# backscatter_tag_v2.net
KiCad netlist of a schematic drawn in EAGLE
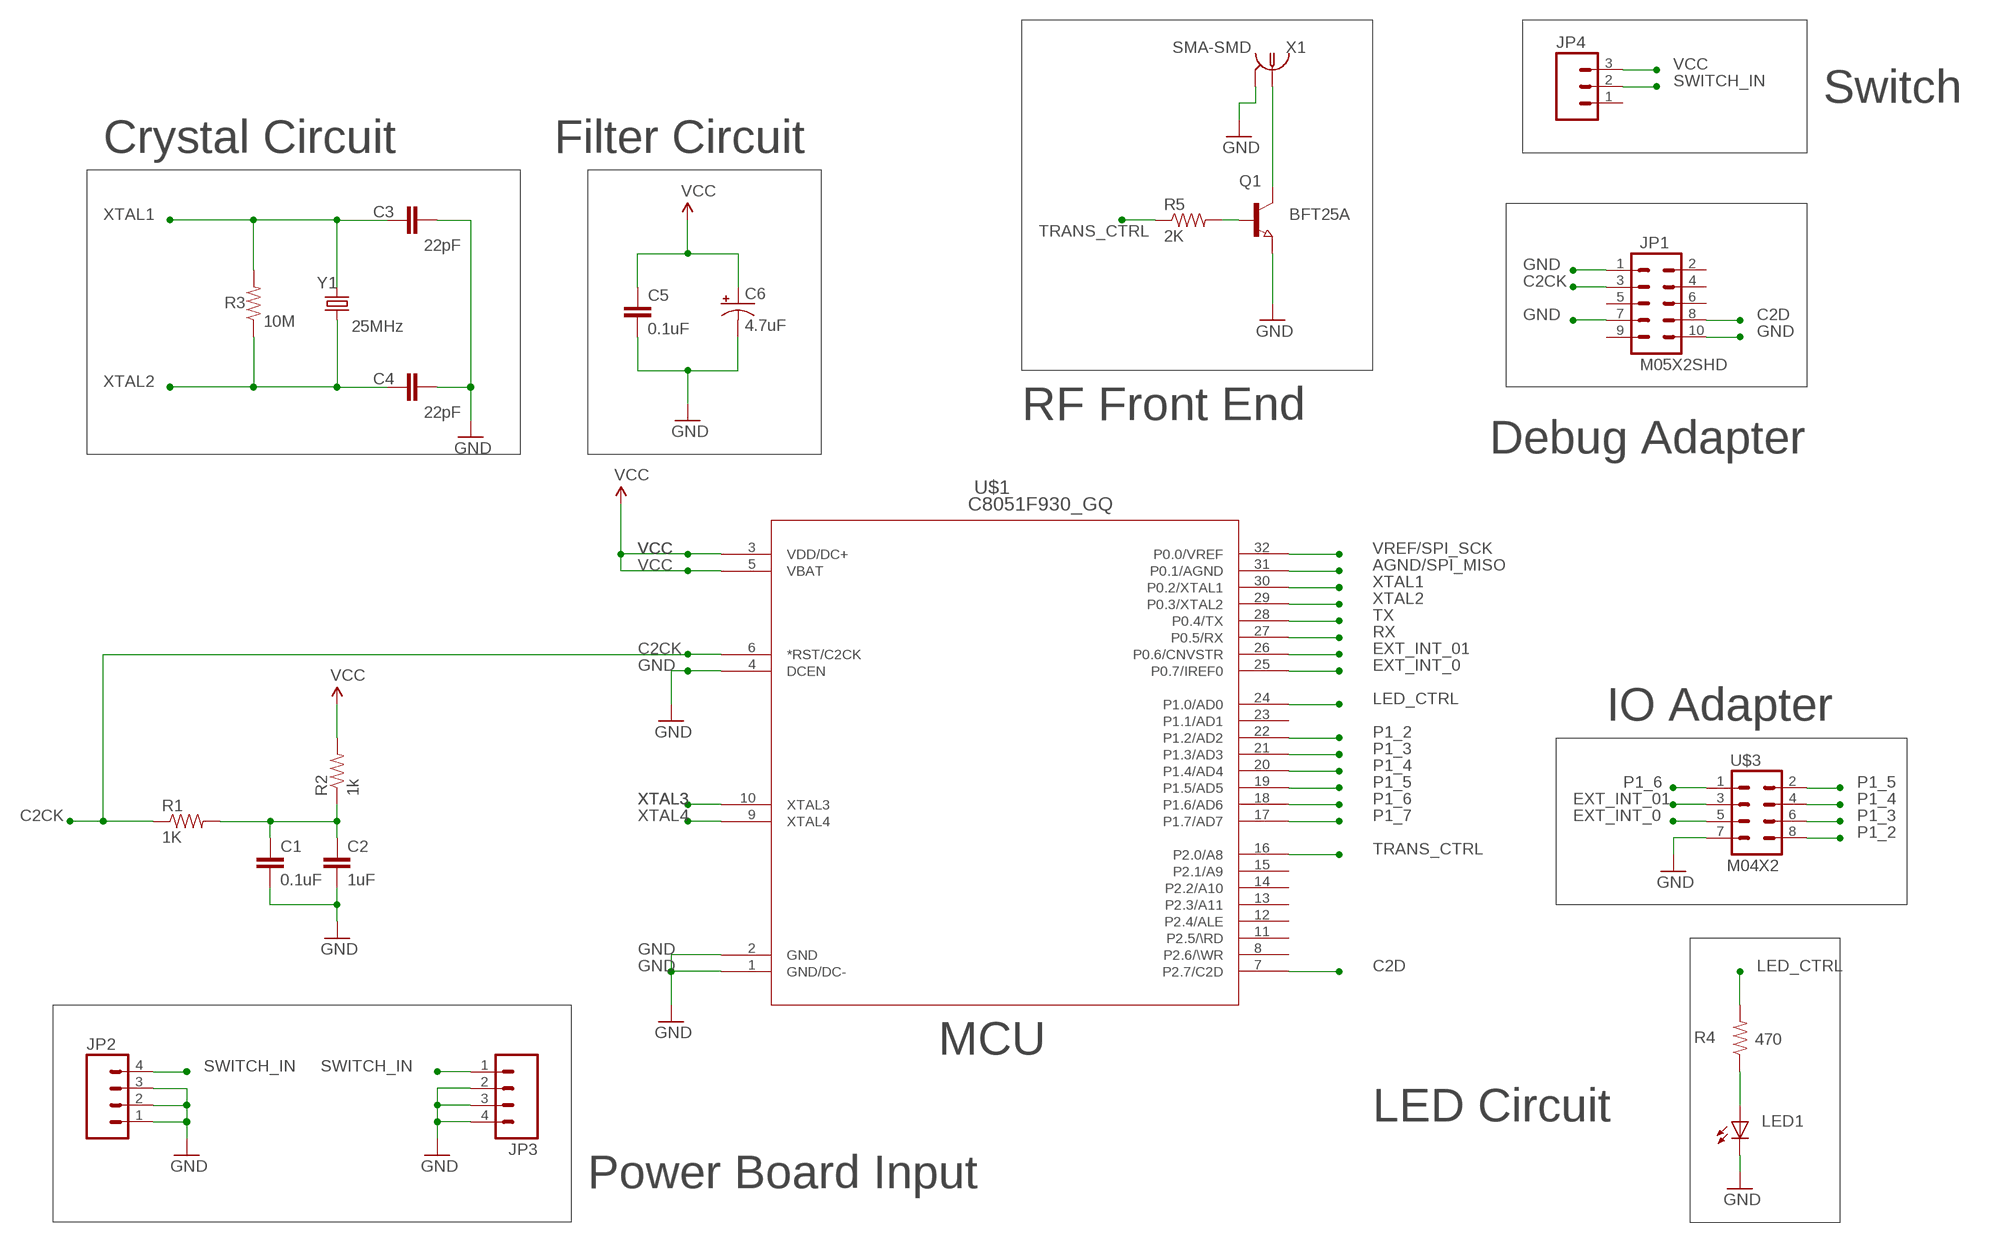
[diagram p0: schematic, sheet 1]

(export (version "E")
  (design (tool "Eeschema 10.0.6"))
  (components
    (comp (ref "C1")
      (value "0.1uF")
      (footprint "eagle-import:0805")
      (libsource (lib "eagle-import") (part "CAP0805"))
    )
    (comp (ref "C2")
      (value "1uF")
      (footprint "eagle-import:0805")
      (libsource (lib "eagle-import") (part "CAP0805"))
    )
    (comp (ref "C3")
      (value "22pF")
      (footprint "eagle-import:0805")
      (libsource (lib "eagle-import") (part "SparkFun-Capacitors_CAP0805"))
    )
    (comp (ref "C4")
      (value "22pF")
      (footprint "eagle-import:0805")
      (libsource (lib "eagle-import") (part "SparkFun-Capacitors_CAP0805"))
    )
    (comp (ref "C5")
      (value "0.1uF")
      (footprint "eagle-import:0805")
      (libsource (lib "eagle-import") (part "SparkFun-Capacitors_CAP0805"))
    )
    (comp (ref "C6")
      (value "4.7uF")
      (footprint "eagle-import:EIA3216")
      (libsource (lib "eagle-import") (part "CAP_POL1206"))
    )
    (comp (ref "JP1")
      (value "M05X2SHD")
      (footprint "eagle-import:2X5-SHROUDED")
      (libsource (lib "eagle-import") (part "M05X2SHD"))
    )
    (comp (ref "JP2")
      (value "M04LOCK")
      (footprint "eagle-import:1X04_LOCK")
      (libsource (lib "eagle-import") (part "M04LOCK"))
    )
    (comp (ref "JP3")
      (value "M04LOCK")
      (footprint "eagle-import:1X04_LOCK")
      (libsource (lib "eagle-import") (part "M04LOCK"))
    )
    (comp (ref "JP4")
      (value "M03LOCK")
      (footprint "eagle-import:1X03_LOCK")
      (libsource (lib "eagle-import") (part "M03LOCK"))
    )
    (comp (ref "LED1")
      (value "LED-FKIT-1206")
      (footprint "eagle-import:FKIT-LED-1206")
      (libsource (lib "eagle-import") (part "LED-FKIT-1206"))
    )
    (comp (ref "Q1")
      (value "BFT25A")
      (footprint "eagle-import:SOT23")
      (libsource (lib "eagle-import") (part "NPN-TRANSISTOR_SOT23"))
    )
    (comp (ref "R1")
      (value "1K")
      (footprint "eagle-import:0805")
      (libsource (lib "eagle-import") (part "RESISTOR0805-RES"))
    )
    (comp (ref "R2")
      (value "1k")
      (footprint "eagle-import:0805")
      (libsource (lib "eagle-import") (part "RESISTOR0805-RES"))
    )
    (comp (ref "R3")
      (value "10M")
      (footprint "eagle-import:0805")
      (libsource (lib "eagle-import") (part "SparkFun-Resistors_RESISTOR0805-RES"))
    )
    (comp (ref "R4")
      (value "470")
      (footprint "eagle-import:0805")
      (libsource (lib "eagle-import") (part "SparkFun-Resistors_RESISTOR0805-RES"))
    )
    (comp (ref "R5")
      (value "2K")
      (footprint "eagle-import:0603-RES")
      (libsource (lib "eagle-import") (part "SparkFun-Resistors_RESISTOR0603-RES"))
    )
    (comp (ref "U$1")
      (value "C8051F930_GQ")
      (footprint "eagle-import:QFP32-7X7-0P8MM")
      (libsource (lib "eagle-import") (part "C8051F930_GQ"))
    )
    (comp (ref "U$3")
      (value "M04X2")
      (footprint "eagle-import:2X4")
      (libsource (lib "eagle-import") (part "M04X2"))
    )
    (comp (ref "X1")
      (value "SMA-SMD")
      (footprint "eagle-import:SMA-SMD")
      (libsource (lib "eagle-import") (part "SMA-SMD"))
    )
    (comp (ref "Y1")
      (value "25MHz")
      (footprint "eagle-import:HC49US")
      (libsource (lib "eagle-import") (part "CRYSTALHC49US"))
    )
  )
  (nets
    (net (code "1") (name "/AGND{slash}SPI_MISO") (class "Default")
      (node (ref "U$1") (pin "31") (pinfunction "P0.1/AGND_31") (pintype "passive"))
    )
    (net (code "2") (name "/C2CK") (class "Default")
      (node (ref "JP1") (pin "3") (pinfunction "3_3") (pintype "passive"))
      (node (ref "R1") (pin "1") (pinfunction "1_1") (pintype "passive"))
      (node (ref "U$1") (pin "6") (pinfunction "*RST/C2CK_6") (pintype "passive"))
    )
    (net (code "3") (name "/C2D") (class "Default")
      (node (ref "JP1") (pin "8") (pinfunction "8_8") (pintype "passive"))
      (node (ref "U$1") (pin "7") (pinfunction "P2.7/C2D_7") (pintype "passive"))
    )
    (net (code "4") (name "/EXT_INT_0") (class "Default")
      (node (ref "U$1") (pin "25") (pinfunction "P0.7/IREF0_25") (pintype "passive"))
      (node (ref "U$3") (pin "5") (pinfunction "5_5") (pintype "passive"))
    )
    (net (code "5") (name "/EXT_INT_01") (class "Default")
      (node (ref "U$1") (pin "26") (pinfunction "P0.6/CNVSTR_26") (pintype "passive"))
      (node (ref "U$3") (pin "3") (pinfunction "3_3") (pintype "passive"))
    )
    (net (code "6") (name "/LED_CTRL") (class "Default")
      (node (ref "R4") (pin "2") (pinfunction "2_2") (pintype "passive"))
      (node (ref "U$1") (pin "24") (pinfunction "P1.0/AD0_24") (pintype "passive"))
    )
    (net (code "7") (name "/P1_2") (class "Default")
      (node (ref "U$1") (pin "22") (pinfunction "P1.2/AD2_22") (pintype "passive"))
      (node (ref "U$3") (pin "8") (pinfunction "8_8") (pintype "passive"))
    )
    (net (code "8") (name "/P1_3") (class "Default")
      (node (ref "U$1") (pin "21") (pinfunction "P1.3/AD3_21") (pintype "passive"))
      (node (ref "U$3") (pin "6") (pinfunction "6_6") (pintype "passive"))
    )
    (net (code "9") (name "/P1_4") (class "Default")
      (node (ref "U$1") (pin "20") (pinfunction "P1.4/AD4_20") (pintype "passive"))
      (node (ref "U$3") (pin "4") (pinfunction "4_4") (pintype "passive"))
    )
    (net (code "10") (name "/P1_5") (class "Default")
      (node (ref "U$1") (pin "19") (pinfunction "P1.5/AD5_19") (pintype "passive"))
      (node (ref "U$3") (pin "2") (pinfunction "2_2") (pintype "passive"))
    )
    (net (code "11") (name "/P1_6") (class "Default")
      (node (ref "U$1") (pin "18") (pinfunction "P1.6/AD6_18") (pintype "passive"))
      (node (ref "U$3") (pin "1") (pinfunction "1_1") (pintype "passive"))
    )
    (net (code "12") (name "/P1_7") (class "Default")
      (node (ref "U$1") (pin "17") (pinfunction "P1.7/AD7_17") (pintype "passive"))
    )
    (net (code "13") (name "/RX") (class "Default")
      (node (ref "U$1") (pin "27") (pinfunction "P0.5/RX_27") (pintype "passive"))
    )
    (net (code "14") (name "/SWITCH_IN") (class "Default")
      (node (ref "JP2") (pin "4") (pinfunction "4_4") (pintype "passive"))
      (node (ref "JP3") (pin "1") (pinfunction "1_1") (pintype "passive"))
      (node (ref "JP4") (pin "2") (pinfunction "2_2") (pintype "passive"))
    )
    (net (code "15") (name "/TRANS_CTRL") (class "Default")
      (node (ref "R5") (pin "1") (pinfunction "1_1") (pintype "passive"))
      (node (ref "U$1") (pin "16") (pinfunction "P2.0/A8_16") (pintype "passive"))
    )
    (net (code "16") (name "/TX") (class "Default")
      (node (ref "U$1") (pin "28") (pinfunction "P0.4/TX_28") (pintype "passive"))
    )
    (net (code "17") (name "/VREF{slash}SPI_SCK") (class "Default")
      (node (ref "U$1") (pin "32") (pinfunction "P0.0/VREF_32") (pintype "passive"))
    )
    (net (code "18") (name "/XTAL1") (class "Default")
      (node (ref "C3") (pin "1") (pinfunction "1_1") (pintype "passive"))
      (node (ref "R3") (pin "2") (pinfunction "2_2") (pintype "passive"))
      (node (ref "U$1") (pin "30") (pinfunction "P0.2/XTAL1_30") (pintype "passive"))
      (node (ref "Y1") (pin "2") (pinfunction "2_2") (pintype "passive"))
    )
    (net (code "19") (name "/XTAL2") (class "Default")
      (node (ref "C4") (pin "1") (pinfunction "1_1") (pintype "passive"))
      (node (ref "R3") (pin "1") (pinfunction "1_1") (pintype "passive"))
      (node (ref "U$1") (pin "29") (pinfunction "P0.3/XTAL2_29") (pintype "passive"))
      (node (ref "Y1") (pin "1") (pinfunction "1_1") (pintype "passive"))
    )
    (net (code "20") (name "/XTAL3") (class "Default")
      (node (ref "U$1") (pin "10") (pinfunction "XTAL3_10") (pintype "passive"))
    )
    (net (code "21") (name "/XTAL4") (class "Default")
      (node (ref "U$1") (pin "9") (pinfunction "XTAL4_9") (pintype "passive"))
    )
    (net (code "22") (name "GND") (class "Default")
      (node (ref "C1") (pin "2") (pinfunction "2_2") (pintype "passive"))
      (node (ref "C2") (pin "2") (pinfunction "2_2") (pintype "passive"))
      (node (ref "C3") (pin "2") (pinfunction "2_2") (pintype "passive"))
      (node (ref "C4") (pin "2") (pinfunction "2_2") (pintype "passive"))
      (node (ref "C5") (pin "2") (pinfunction "2_2") (pintype "passive"))
      (node (ref "C6") (pin "C") (pinfunction "-_C") (pintype "passive"))
      (node (ref "JP1") (pin "1") (pinfunction "1_1") (pintype "passive"))
      (node (ref "JP1") (pin "10") (pinfunction "10_10") (pintype "passive"))
      (node (ref "JP1") (pin "7") (pinfunction "7_7") (pintype "passive"))
      (node (ref "JP2") (pin "1") (pinfunction "1_1") (pintype "passive"))
      (node (ref "JP2") (pin "2") (pinfunction "2_2") (pintype "passive"))
      (node (ref "JP2") (pin "3") (pinfunction "3_3") (pintype "passive"))
      (node (ref "JP3") (pin "2") (pinfunction "2_2") (pintype "passive"))
      (node (ref "JP3") (pin "3") (pinfunction "3_3") (pintype "passive"))
      (node (ref "JP3") (pin "4") (pinfunction "4_4") (pintype "passive"))
      (node (ref "LED1") (pin "C") (pinfunction "C_C") (pintype "passive"))
      (node (ref "Q1") (pin "2") (pinfunction "E_2") (pintype "passive"))
      (node (ref "U$1") (pin "1") (pinfunction "GND/DC-_1") (pintype "passive"))
      (node (ref "U$1") (pin "2") (pinfunction "GND_2") (pintype "passive"))
      (node (ref "U$1") (pin "4") (pinfunction "DCEN_4") (pintype "passive"))
      (node (ref "U$3") (pin "7") (pinfunction "7_7") (pintype "passive"))
      (node (ref "X1") (pin "2@1") (pinfunction "2_2@1") (pintype "passive"))
      (node (ref "X1") (pin "2@2") (pinfunction "2_2@2") (pintype "passive"))
      (node (ref "X1") (pin "2@3") (pinfunction "2_2@3") (pintype "passive"))
      (node (ref "X1") (pin "2@4") (pinfunction "2_2@4") (pintype "passive"))
      (node (ref "X1") (pin "2@5") (pinfunction "2_2@5") (pintype "passive"))
      (node (ref "X1") (pin "2@6") (pinfunction "2_2@6") (pintype "passive"))
    )
    (net (code "23") (name "Net-(C1-Pad1)") (class "Default")
      (node (ref "C1") (pin "1") (pinfunction "1_1") (pintype "passive"))
      (node (ref "C2") (pin "1") (pinfunction "1_1") (pintype "passive"))
      (node (ref "R1") (pin "2") (pinfunction "2_2") (pintype "passive"))
      (node (ref "R2") (pin "1") (pinfunction "1_1") (pintype "passive"))
    )
    (net (code "24") (name "Net-(LED1-PadA)") (class "Default")
      (node (ref "LED1") (pin "A") (pinfunction "A_A") (pintype "passive"))
      (node (ref "R4") (pin "1") (pinfunction "1_1") (pintype "passive"))
    )
    (net (code "25") (name "Net-(Q1-B)") (class "Default")
      (node (ref "Q1") (pin "1") (pinfunction "B_1") (pintype "passive"))
      (node (ref "R5") (pin "2") (pinfunction "2_2") (pintype "passive"))
    )
    (net (code "26") (name "Net-(Q1-C)") (class "Default")
      (node (ref "Q1") (pin "3") (pinfunction "C_3") (pintype "passive"))
      (node (ref "X1") (pin "1") (pinfunction "1_1") (pintype "passive"))
    )
    (net (code "27") (name "VCC") (class "Default")
      (node (ref "C5") (pin "1") (pinfunction "1_1") (pintype "passive"))
      (node (ref "C6") (pin "A") (pinfunction "+_A") (pintype "passive"))
      (node (ref "JP4") (pin "3") (pinfunction "3_3") (pintype "passive"))
      (node (ref "R2") (pin "2") (pinfunction "2_2") (pintype "passive"))
      (node (ref "U$1") (pin "3") (pinfunction "VDD/DC+_3") (pintype "passive"))
      (node (ref "U$1") (pin "5") (pinfunction "VBAT_5") (pintype "passive"))
    )
    (net (code "28") (name "unconnected-(JP1-Pad2)") (class "Default")
      (node (ref "JP1") (pin "2") (pinfunction "2_2") (pintype "passive"))
    )
    (net (code "29") (name "unconnected-(JP1-Pad4)") (class "Default")
      (node (ref "JP1") (pin "4") (pinfunction "4_4") (pintype "passive"))
    )
    (net (code "30") (name "unconnected-(JP1-Pad5)") (class "Default")
      (node (ref "JP1") (pin "5") (pinfunction "5_5") (pintype "passive"))
    )
    (net (code "31") (name "unconnected-(JP1-Pad6)") (class "Default")
      (node (ref "JP1") (pin "6") (pinfunction "6_6") (pintype "passive"))
    )
    (net (code "32") (name "unconnected-(JP1-Pad9)") (class "Default")
      (node (ref "JP1") (pin "9") (pinfunction "9_9") (pintype "passive"))
    )
    (net (code "33") (name "unconnected-(JP4-Pad1)") (class "Default")
      (node (ref "JP4") (pin "1") (pinfunction "1_1") (pintype "passive"))
    )
    (net (code "34") (name "unconnected-(U$1-P1.1{slash}AD1-Pad23)") (class "Default")
      (node (ref "U$1") (pin "23") (pinfunction "P1.1/AD1_23") (pintype "passive"))
    )
    (net (code "35") (name "unconnected-(U$1-P2.1{slash}A9-Pad15)") (class "Default")
      (node (ref "U$1") (pin "15") (pinfunction "P2.1/A9_15") (pintype "passive"))
    )
    (net (code "36") (name "unconnected-(U$1-P2.2{slash}A10-Pad14)") (class "Default")
      (node (ref "U$1") (pin "14") (pinfunction "P2.2/A10_14") (pintype "passive"))
    )
    (net (code "37") (name "unconnected-(U$1-P2.3{slash}A11-Pad13)") (class "Default")
      (node (ref "U$1") (pin "13") (pinfunction "P2.3/A11_13") (pintype "passive"))
    )
    (net (code "38") (name "unconnected-(U$1-P2.4{slash}ALE-Pad12)") (class "Default")
      (node (ref "U$1") (pin "12") (pinfunction "P2.4/ALE_12") (pintype "passive"))
    )
    (net (code "39") (name "unconnected-(U$1-P2.5{slash}\\RD-Pad11)") (class "Default")
      (node (ref "U$1") (pin "11") (pinfunction "P2.5/\\RD_11") (pintype "passive"))
    )
    (net (code "40") (name "unconnected-(U$1-P2.6{slash}\\WR-Pad8)") (class "Default")
      (node (ref "U$1") (pin "8") (pinfunction "P2.6/\\WR_8") (pintype "passive"))
    )
  )
)
